# H1maria_v5.net
KiCad netlist of a schematic drawn in EAGLE
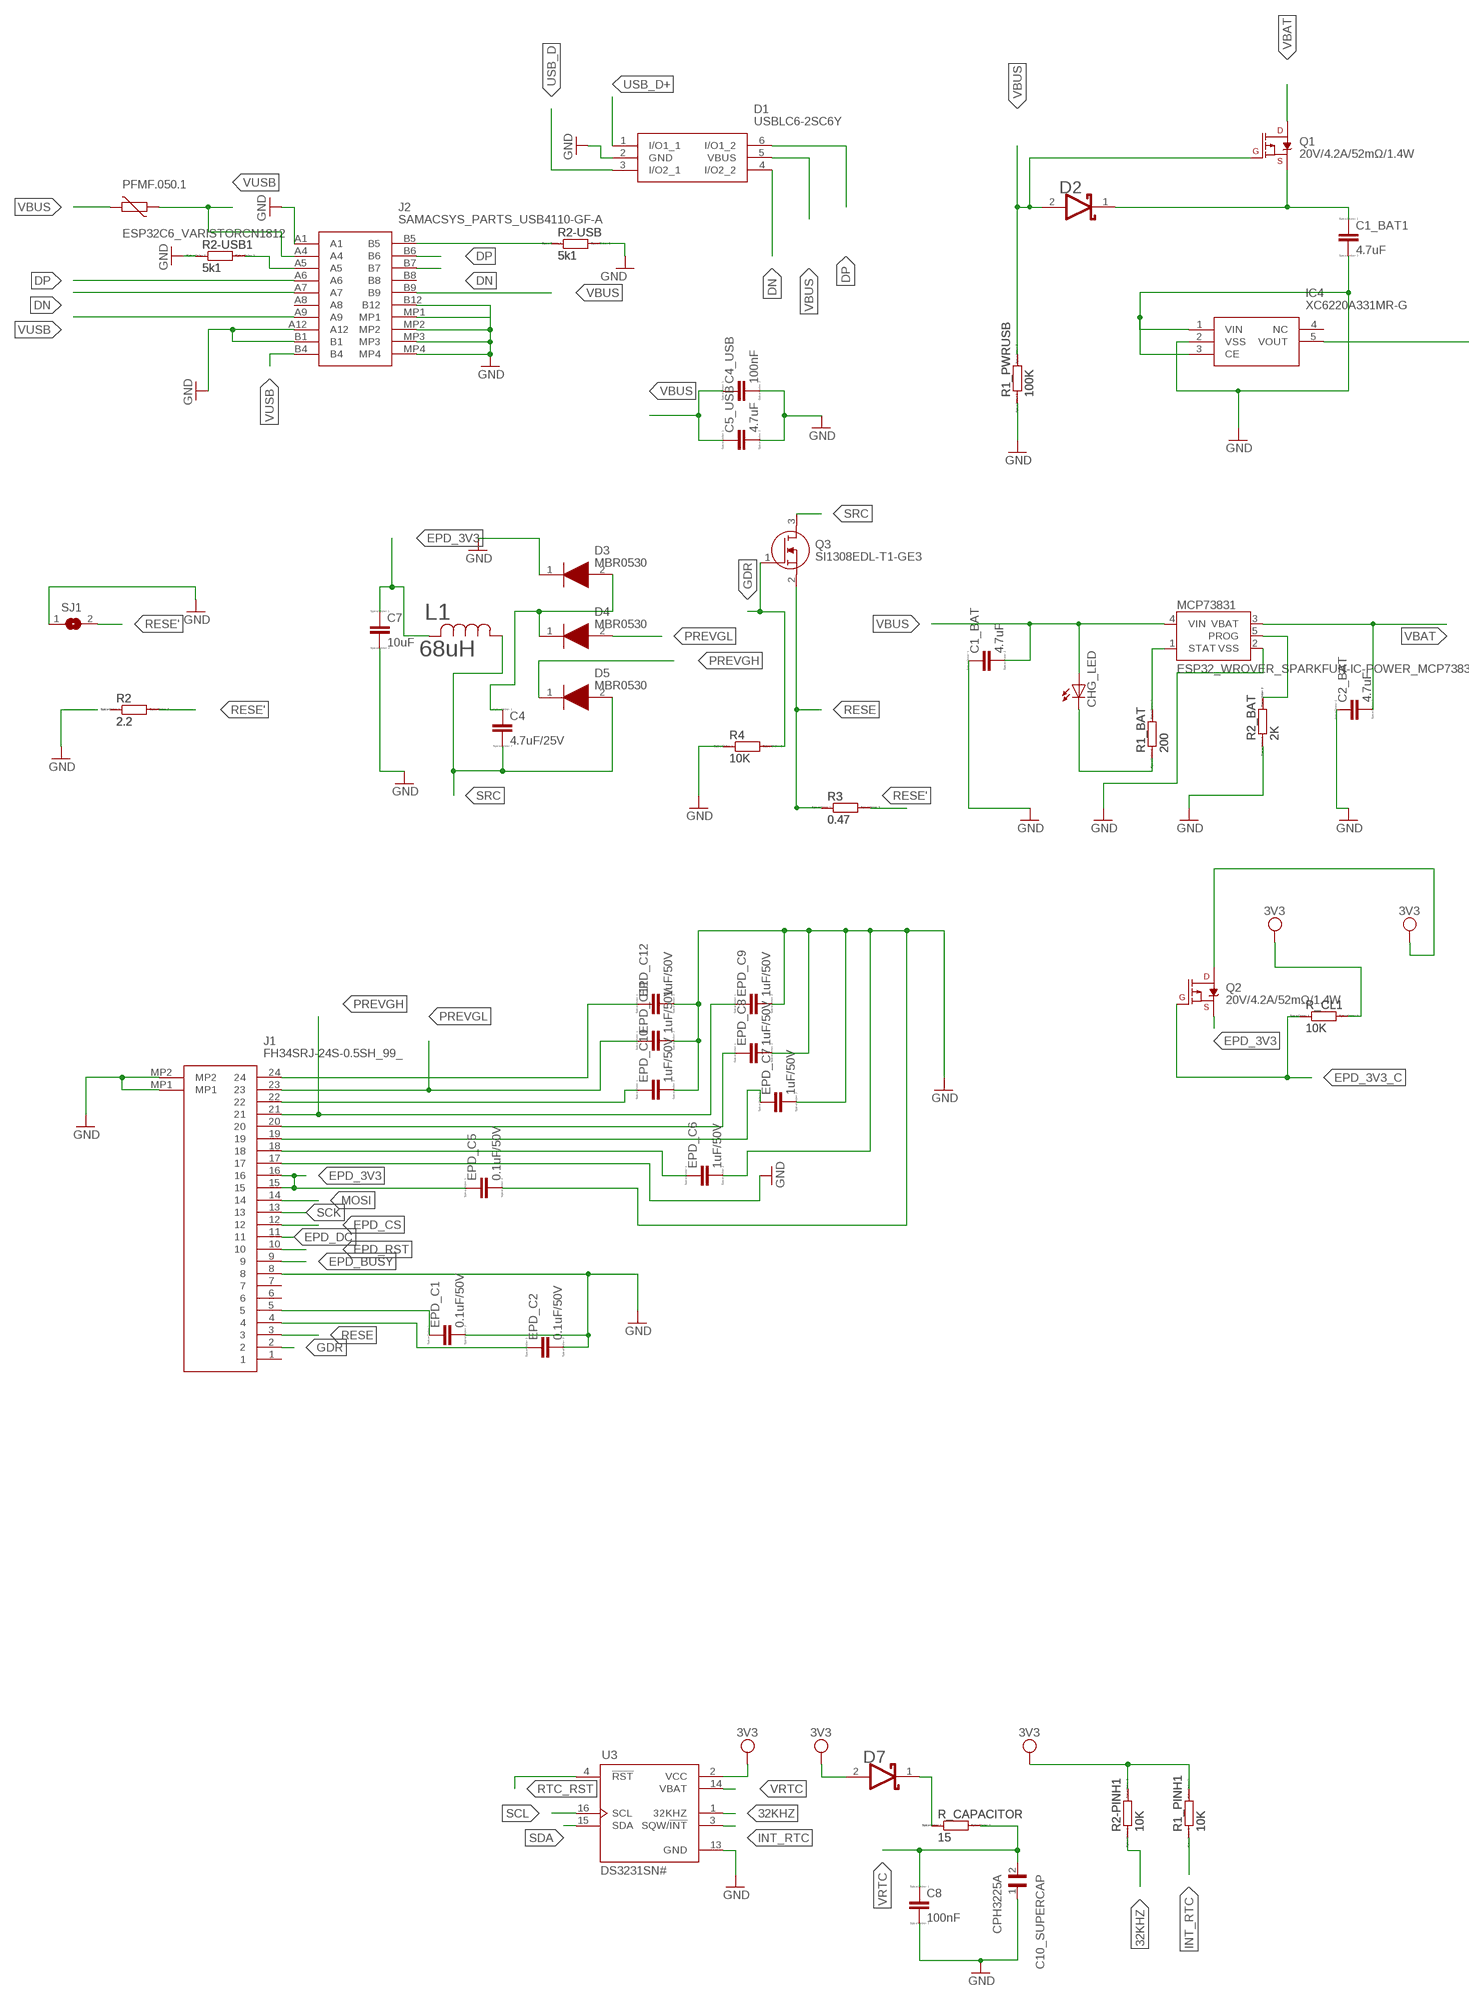
[diagram p0: schematic, sheet 1, part 1 of 2]
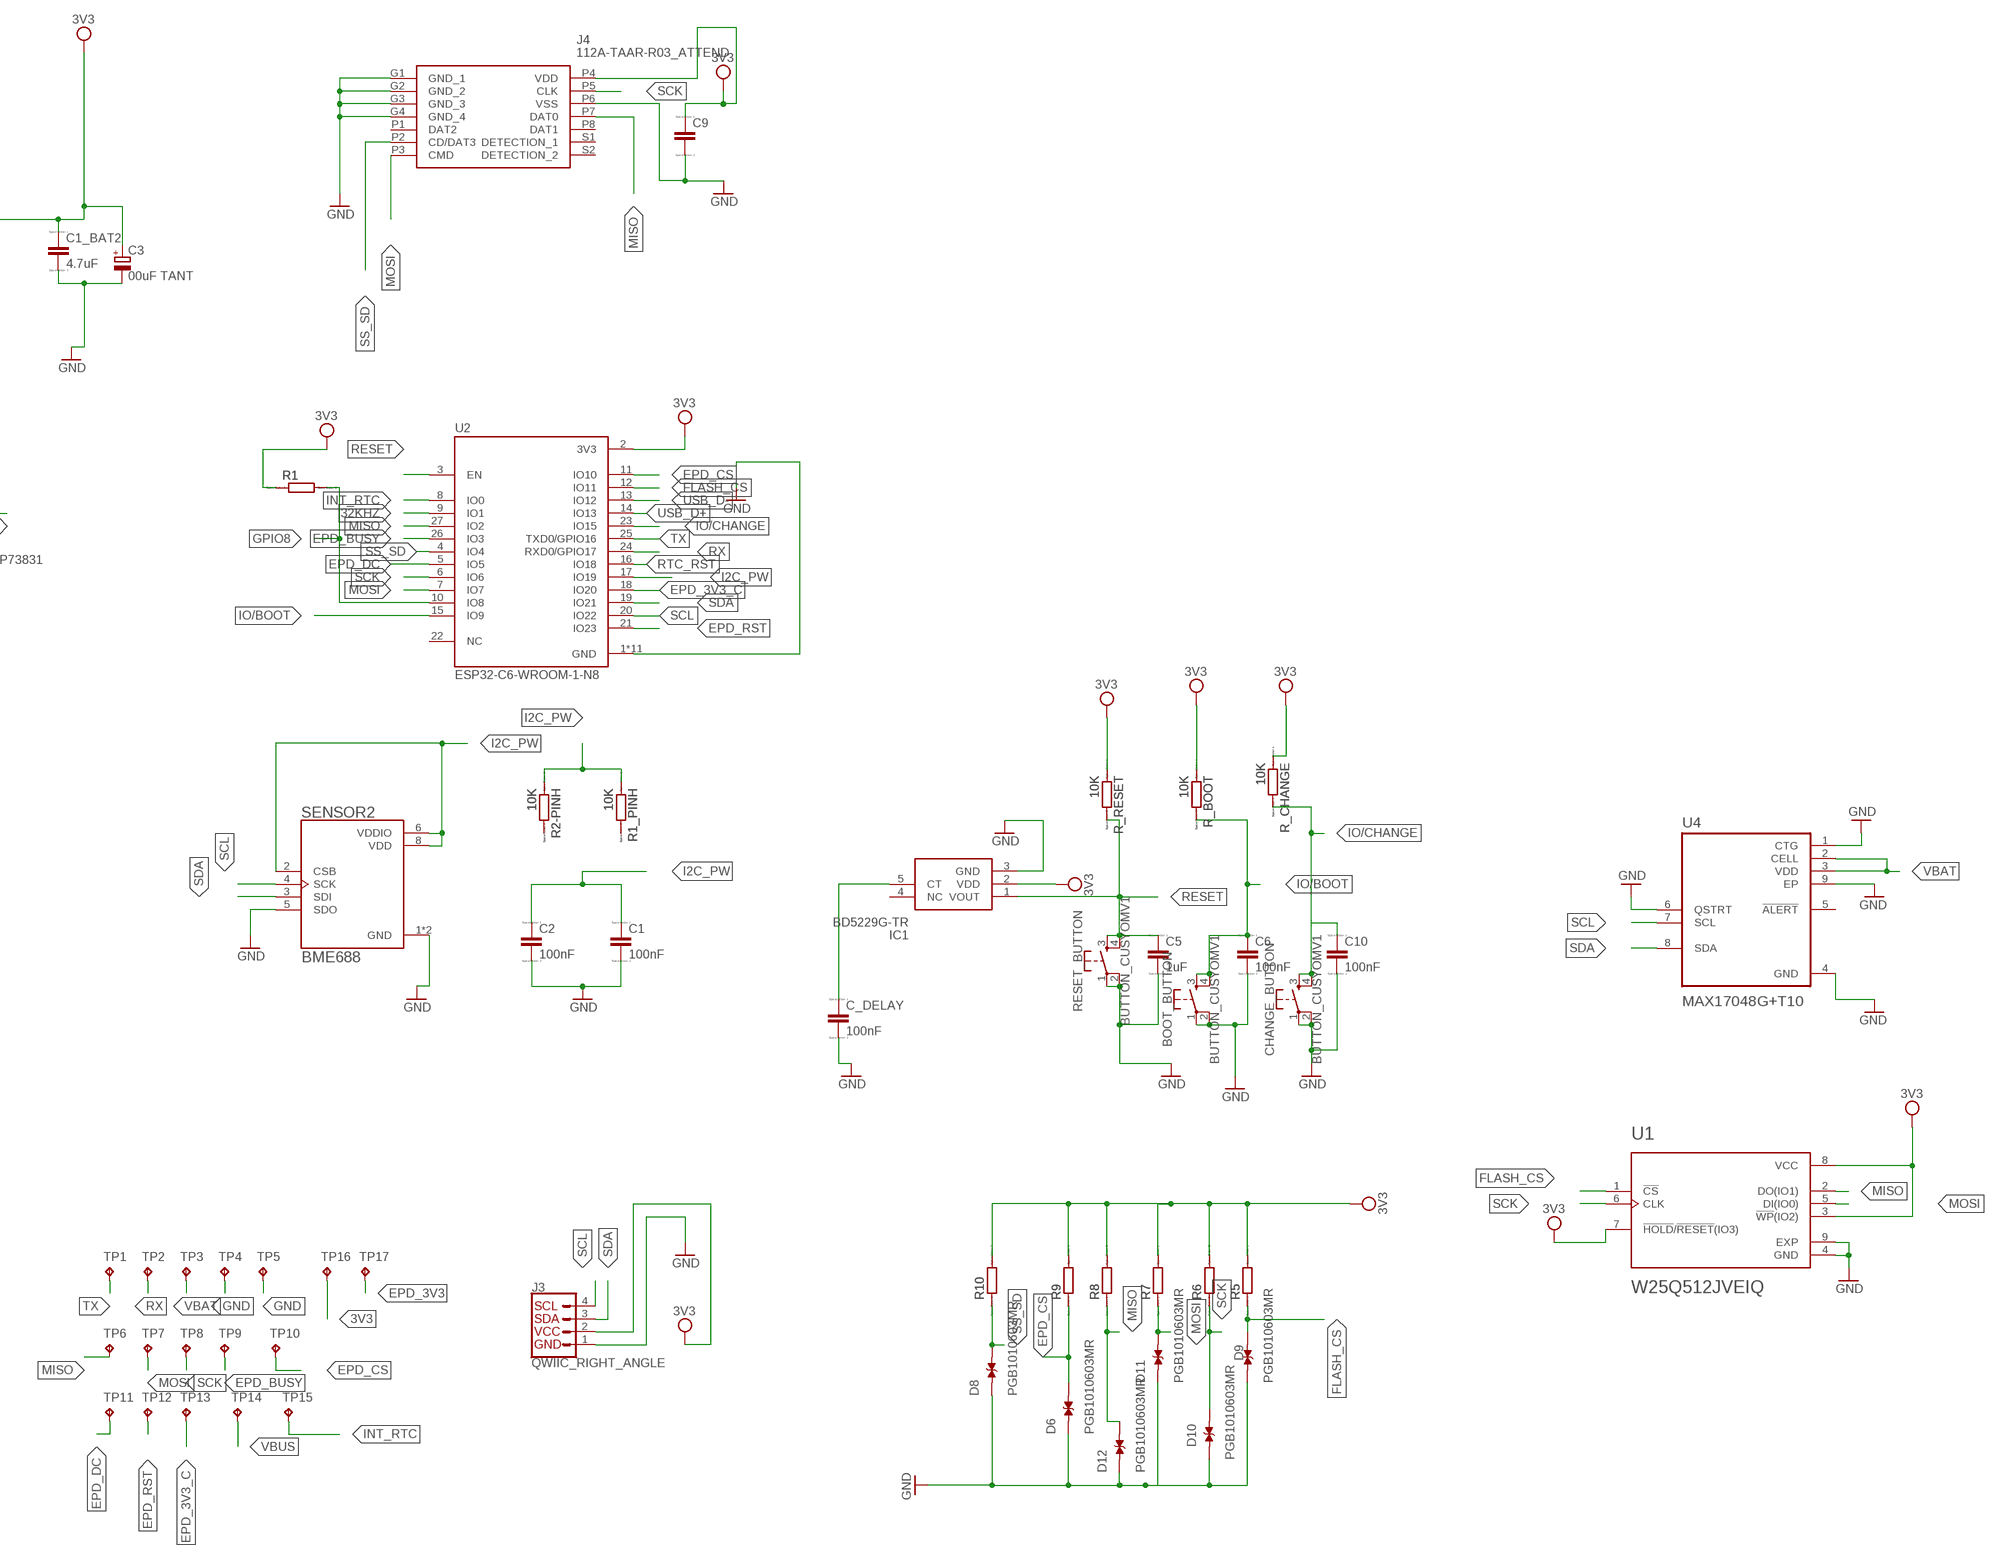
[diagram p1: schematic, sheet 1, part 2 of 2]

(export (version "E")
  (design (tool "Eeschema 10.0.6"))
  (components
    (comp (ref "BOOT_BUTTON")
      (value "BUTTON_CUSYOMV1")
      (footprint "eagle-import:MYBUTTON")
      (libsource (lib "eagle-import") (part "BUTTON_CUSYOMV1"))
    )
    (comp (ref "C1")
      (value "100nF")
      (footprint "eagle-import:ESP32_WROVER_EAGLE-LTSPICE_C0402")
      (libsource (lib "eagle-import") (part "ESP32_WROVER_EAGLE-LTSPICE_CC0402"))
    )
    (comp (ref "C1_BAT")
      (value "4.7uF")
      (footprint "eagle-import:EAGLE-LTSPICE_C0402")
      (libsource (lib "eagle-import") (part "EAGLE-LTSPICE_CC0402"))
    )
    (comp (ref "C1_BAT1")
      (value "4.7uF")
      (footprint "eagle-import:EAGLE-LTSPICE_C0402")
      (libsource (lib "eagle-import") (part "EAGLE-LTSPICE_CC0402"))
    )
    (comp (ref "C1_BAT2")
      (value "4.7uF")
      (footprint "eagle-import:EAGLE-LTSPICE_C0402")
      (libsource (lib "eagle-import") (part "EAGLE-LTSPICE_CC0402"))
    )
    (comp (ref "C2")
      (value "100nF")
      (footprint "eagle-import:ESP32_WROVER_EAGLE-LTSPICE_C0402")
      (libsource (lib "eagle-import") (part "ESP32_WROVER_EAGLE-LTSPICE_CC0402"))
    )
    (comp (ref "C2_BAT")
      (value "4.7uF")
      (footprint "eagle-import:EAGLE-LTSPICE_C0402")
      (libsource (lib "eagle-import") (part "EAGLE-LTSPICE_CC0402"))
    )
    (comp (ref "C3")
      (value "00uF TANT")
      (footprint "eagle-import:RCL_CT3528")
      (libsource (lib "eagle-import") (part "RCL_CPOL-EUCT3528"))
    )
    (comp (ref "C4")
      (value "4.7uF/25V")
      (footprint "eagle-import:ESP32_WROVER_EAGLE-LTSPICE_C0402")
      (libsource (lib "eagle-import") (part "ESP32_WROVER_EAGLE-LTSPICE_CC0402"))
    )
    (comp (ref "C4_USB")
      (value "100nF")
      (footprint "eagle-import:EAGLE-LTSPICE_C0402")
      (libsource (lib "eagle-import") (part "EAGLE-LTSPICE_CC0402"))
    )
    (comp (ref "C5")
      (value "1uF")
      (footprint "eagle-import:EAGLE-LTSPICE_C0402")
      (libsource (lib "eagle-import") (part "EAGLE-LTSPICE_CC0402"))
    )
    (comp (ref "C5_USB")
      (value "4.7uF")
      (footprint "eagle-import:EAGLE-LTSPICE_C0402")
      (libsource (lib "eagle-import") (part "EAGLE-LTSPICE_CC0402"))
    )
    (comp (ref "C6")
      (value "100nF")
      (footprint "eagle-import:EAGLE-LTSPICE_C0402")
      (libsource (lib "eagle-import") (part "EAGLE-LTSPICE_CC0402"))
    )
    (comp (ref "C7")
      (value "10uF")
      (footprint "eagle-import:ESP32_WROVER_EAGLE-LTSPICE_C0402")
      (libsource (lib "eagle-import") (part "ESP32_WROVER_EAGLE-LTSPICE_CC0402"))
    )
    (comp (ref "C8")
      (value "100nF")
      (footprint "eagle-import:EAGLE-LTSPICE_C0402")
      (libsource (lib "eagle-import") (part "EAGLE-LTSPICE_CC0402"))
    )
    (comp (ref "C9")
      (value "ESP32_WROVER_EAGLE-LTSPICE_CC0402")
      (footprint "eagle-import:ESP32_WROVER_EAGLE-LTSPICE_C0402")
      (libsource (lib "eagle-import") (part "ESP32_WROVER_EAGLE-LTSPICE_CC0402"))
    )
    (comp (ref "C10")
      (value "100nF")
      (footprint "eagle-import:EAGLE-LTSPICE_C0402")
      (libsource (lib "eagle-import") (part "EAGLE-LTSPICE_CC0402"))
    )
    (comp (ref "C10_SUPERCAP")
      (value "CPH3225A")
      (footprint "eagle-import:CAPCP3225X100N")
      (fields (field (name "MF") "Seiko Instruments"))
      (libsource (lib "eagle-import") (part "CPH3225A"))
    )
    (comp (ref "CHANGE_BUTTON")
      (value "BUTTON_CUSYOMV1")
      (footprint "eagle-import:MYBUTTON")
      (libsource (lib "eagle-import") (part "BUTTON_CUSYOMV1"))
    )
    (comp (ref "CHG_LED")
      (value "ADAFRUIT_LEDCHIP-LED0603")
      (footprint "eagle-import:ADAFRUIT_CHIP-LED0603")
      (libsource (lib "eagle-import") (part "ADAFRUIT_LEDCHIP-LED0603"))
    )
    (comp (ref "C_DELAY")
      (value "100nF")
      (footprint "eagle-import:EAGLE-LTSPICE_C0402")
      (libsource (lib "eagle-import") (part "EAGLE-LTSPICE_CC0402"))
    )
    (comp (ref "D1")
      (value "USBLC6-2SC6Y")
      (footprint "eagle-import:SOT95P280X145-6N")
      (fields (field (name "MF") "STMicroelectronics"))
      (libsource (lib "eagle-import") (part "USBLC6-2SC6Y"))
    )
    (comp (ref "D2")
      (value "SD0805S020S1R0")
      (footprint "eagle-import:ESP32_WROVER_AVX---SD0805S020S1R0_AVX_SD0805S020S1R0_0")
      (fields
        (field (name "DIGIKEY_PART_NUMBER") "478-7800-1-ND")
        (field (name "MF") "AVX")
        (field (name "MOUSER_PART_NUMBER") "581-SD0805S020S1R0")
      )
      (libsource (lib "eagle-import") (part "ESP32_WROVER_AVX---SD0805S020S1R0_AVX_SD0805S020S1R0_0_0AVX_SD0805S020S1R0_0_0"))
    )
    (comp (ref "D3")
      (value "MBR0530")
      (footprint "eagle-import:SOD3716X135N")
      (fields (field (name "MF") "ON Semiconductor"))
      (libsource (lib "eagle-import") (part "MBR0530"))
    )
    (comp (ref "D4")
      (value "MBR0530")
      (footprint "eagle-import:SOD3716X135N")
      (fields (field (name "MF") "ON Semiconductor"))
      (libsource (lib "eagle-import") (part "MBR0530"))
    )
    (comp (ref "D5")
      (value "MBR0530")
      (footprint "eagle-import:SOD3716X135N")
      (fields (field (name "MF") "ON Semiconductor"))
      (libsource (lib "eagle-import") (part "MBR0530"))
    )
    (comp (ref "D6")
      (value "PGB1010603MR")
      (footprint "eagle-import:DIOC1608X36N")
      (fields (field (name "MF") "Littelfuse Inc."))
      (libsource (lib "eagle-import") (part "PGB1010603MR"))
    )
    (comp (ref "D7")
      (value "ESP32_WROVER_AVX---SD0805S020S1R0_AVX_SD0805S020S1R0_0_0AVX_SD0805S020S1R0_0_0")
      (footprint "eagle-import:ESP32_WROVER_AVX---SD0805S020S1R0_AVX_SD0805S020S1R0_0")
      (fields
        (field (name "DIGIKEY_PART_NUMBER") "478-7800-1-ND")
        (field (name "MF") "AVX")
        (field (name "MOUSER_PART_NUMBER") "581-SD0805S020S1R0")
      )
      (libsource (lib "eagle-import") (part "ESP32_WROVER_AVX---SD0805S020S1R0_AVX_SD0805S020S1R0_0_0AVX_SD0805S020S1R0_0_0"))
    )
    (comp (ref "D8")
      (value "PGB1010603MR")
      (footprint "eagle-import:DIOC1608X36N")
      (fields (field (name "MF") "Littelfuse Inc."))
      (libsource (lib "eagle-import") (part "PGB1010603MR"))
    )
    (comp (ref "D9")
      (value "PGB1010603MR")
      (footprint "eagle-import:DIOC1608X36N")
      (fields (field (name "MF") "Littelfuse Inc."))
      (libsource (lib "eagle-import") (part "PGB1010603MR"))
    )
    (comp (ref "D10")
      (value "PGB1010603MR")
      (footprint "eagle-import:DIOC1608X36N")
      (fields (field (name "MF") "Littelfuse Inc."))
      (libsource (lib "eagle-import") (part "PGB1010603MR"))
    )
    (comp (ref "D11")
      (value "PGB1010603MR")
      (footprint "eagle-import:DIOC1608X36N")
      (fields (field (name "MF") "Littelfuse Inc."))
      (libsource (lib "eagle-import") (part "PGB1010603MR"))
    )
    (comp (ref "D12")
      (value "PGB1010603MR")
      (footprint "eagle-import:DIOC1608X36N")
      (fields (field (name "MF") "Littelfuse Inc."))
      (libsource (lib "eagle-import") (part "PGB1010603MR"))
    )
    (comp (ref "EPD_C1")
      (value "0.1uF/50V")
      (footprint "eagle-import:EAGLE-LTSPICE_C0402")
      (libsource (lib "eagle-import") (part "EAGLE-LTSPICE_CC0402"))
    )
    (comp (ref "EPD_C2")
      (value "0.1uF/50V")
      (footprint "eagle-import:EAGLE-LTSPICE_C0402")
      (libsource (lib "eagle-import") (part "EAGLE-LTSPICE_CC0402"))
    )
    (comp (ref "EPD_C5")
      (value "0.1uF/50V")
      (footprint "eagle-import:EAGLE-LTSPICE_C0402")
      (libsource (lib "eagle-import") (part "EAGLE-LTSPICE_CC0402"))
    )
    (comp (ref "EPD_C6")
      (value "1uF/50V")
      (footprint "eagle-import:EAGLE-LTSPICE_C0402")
      (libsource (lib "eagle-import") (part "EAGLE-LTSPICE_CC0402"))
    )
    (comp (ref "EPD_C7")
      (value "1uF/50V")
      (footprint "eagle-import:EAGLE-LTSPICE_C0402")
      (libsource (lib "eagle-import") (part "EAGLE-LTSPICE_CC0402"))
    )
    (comp (ref "EPD_C8")
      (value "1uF/50V")
      (footprint "eagle-import:EAGLE-LTSPICE_C0402")
      (libsource (lib "eagle-import") (part "EAGLE-LTSPICE_CC0402"))
    )
    (comp (ref "EPD_C9")
      (value "1uF/50V")
      (footprint "eagle-import:EAGLE-LTSPICE_C0402")
      (libsource (lib "eagle-import") (part "EAGLE-LTSPICE_CC0402"))
    )
    (comp (ref "EPD_C10")
      (value "1uF/50V")
      (footprint "eagle-import:EAGLE-LTSPICE_C0402")
      (libsource (lib "eagle-import") (part "EAGLE-LTSPICE_CC0402"))
    )
    (comp (ref "EPD_C11")
      (value "1uF/50V")
      (footprint "eagle-import:EAGLE-LTSPICE_C0402")
      (libsource (lib "eagle-import") (part "EAGLE-LTSPICE_CC0402"))
    )
    (comp (ref "EPD_C12")
      (value "1uF/50V")
      (footprint "eagle-import:EAGLE-LTSPICE_C0402")
      (libsource (lib "eagle-import") (part "EAGLE-LTSPICE_CC0402"))
    )
    (comp (ref "IC1")
      (value "BD5229G-TR")
      (footprint "eagle-import:SOT95P280X125-5N")
      (fields (field (name "MOUSER_PART_NUMBER") "755-BD5229G-TR"))
      (libsource (lib "eagle-import") (part "BD5229G-TR"))
    )
    (comp (ref "IC4")
      (value "XC6220A331MR-G")
      (footprint "eagle-import:SOT95P280X120-5N")
      (fields (field (name "MOUSER_PART_NUMBER") "865-XC6220A331MR-G"))
      (libsource (lib "eagle-import") (part "XC6220A331MR-G"))
    )
    (comp (ref "J1")
      (value "FH34SRJ-24S-0.5SH_99_")
      (footprint "eagle-import:FH34SRJ24S05SH99")
      (fields
        (field (name "MANUFACTURER_PART_NUMBER") "FH34SRJ-24S-0.5SH(99)")
        (field (name "MOUSER_PART_NUMBER") "798-FH34SRJ24S05SH99")
      )
      (libsource (lib "eagle-import") (part "FH34SRJ-24S-0.5SH_99_"))
    )
    (comp (ref "J2")
      (value "SAMACSYS_PARTS_USB4110-GF-A")
      (footprint "eagle-import:SAMACSYS_PARTS_USB4110GFA")
      (fields
        (field (name "MANUFACTURER_PART_NUMBER") "USB4110-GF-A")
        (field (name "MOUSER_PART_NUMBER") "640-USB4110-GF-A")
      )
      (libsource (lib "eagle-import") (part "SAMACSYS_PARTS_USB4110-GF-A"))
    )
    (comp (ref "J3")
      (value "QWIIC_RIGHT_ANGLE")
      (footprint "eagle-import:JST04_1MM_RA")
      (libsource (lib "eagle-import") (part "QWIIC_CONNECTORJS-1MM"))
    )
    (comp (ref "J4")
      (value "112A-TAAR-R03_ATTEND")
      (footprint "eagle-import:112ATAARR03ATTEND")
      (fields (field (name "MANUFACTURER_PART_NUMBER") "112A-TAAR-R03 ATTEND"))
      (libsource (lib "eagle-import") (part "112A-TAAR-R03_ATTEND"))
    )
    (comp (ref "L1")
      (value "68uH")
      (footprint "eagle-import:IND_4828-WE-TPC_WRE")
      (fields
        (field (name "MANUFACTURER_PART_NUMBER") "744043680")
        (field (name "COPYRIGHT") "Copyright (C) 2024 Ultra Librarian. All rights reserved.")
      )
      (libsource (lib "eagle-import") (part "744043680IND_4828-WE-TPC_WRE"))
    )
    (comp (ref "MCP73831")
      (value "ESP32_WROVER_SPARKFUN-IC-POWER_MCP73831")
      (footprint "eagle-import:ESP32_WROVER_SPARKFUN-IC-POWER_SOT23-5")
      (libsource (lib "eagle-import") (part "ESP32_WROVER_SPARKFUN-IC-POWER_MCP73831"))
    )
    (comp (ref "PFMF.050.1")
      (value "ESP32C6_VARISTORCN1812")
      (footprint "eagle-import:ESP32C6_VARISTOR_CT_CN1812")
      (libsource (lib "eagle-import") (part "ESP32C6_VARISTORCN1812"))
    )
    (comp (ref "Q1")
      (value "20V/4.2A/52mΩ/1.4W")
      (footprint "eagle-import:ESP32_WROVER_SPARKFUN-DISCRETESEMI_SOT23-3")
      (libsource (lib "eagle-import") (part "ESP32_WROVER_SPARKFUN-DISCRETESEMI_MOSFET_PCH-DMG2305UX-7"))
    )
    (comp (ref "Q2")
      (value "20V/4.2A/52mΩ/1.4W")
      (footprint "eagle-import:ESP32_WROVER_SPARKFUN-DISCRETESEMI_SOT23-3")
      (libsource (lib "eagle-import") (part "ESP32_WROVER_SPARKFUN-DISCRETESEMI_MOSFET_PCH-DMG2305UX-7"))
    )
    (comp (ref "Q3")
      (value "SI1308EDL-T1-GE3")
      (footprint "eagle-import:SOT65P210X110-3N")
      (fields (field (name "MF") "Vishay Siliconix"))
      (libsource (lib "eagle-import") (part "SI1308EDL-T1-GE3"))
    )
    (comp (ref "R1")
      (value "ESP32_WROVER_EAGLE-LTSPICE_RR0402")
      (footprint "eagle-import:ESP32_WROVER_EAGLE-LTSPICE_R0402")
      (libsource (lib "eagle-import") (part "ESP32_WROVER_EAGLE-LTSPICE_RR0402"))
    )
    (comp (ref "R1_BAT")
      (value "200")
      (footprint "eagle-import:ESP32_WROVER_EAGLE-LTSPICE_R0402")
      (libsource (lib "eagle-import") (part "ESP32_WROVER_EAGLE-LTSPICE_RR0402"))
    )
    (comp (ref "R1_PINH")
      (value "10K")
      (footprint "eagle-import:ESP32_WROVER_EAGLE-LTSPICE_R0402")
      (libsource (lib "eagle-import") (part "ESP32_WROVER_EAGLE-LTSPICE_RR0402"))
    )
    (comp (ref "R1_PINH1")
      (value "10K")
      (footprint "eagle-import:ESP32_WROVER_EAGLE-LTSPICE_R0402")
      (libsource (lib "eagle-import") (part "ESP32_WROVER_EAGLE-LTSPICE_RR0402"))
    )
    (comp (ref "R1_PWRUSB")
      (value "100K")
      (footprint "eagle-import:ESP32_WROVER_EAGLE-LTSPICE_R0402")
      (libsource (lib "eagle-import") (part "ESP32_WROVER_EAGLE-LTSPICE_RR0402"))
    )
    (comp (ref "R2")
      (value "2.2")
      (footprint "eagle-import:ESP32_WROVER_EAGLE-LTSPICE_R0402")
      (libsource (lib "eagle-import") (part "ESP32_WROVER_EAGLE-LTSPICE_RR0402"))
    )
    (comp (ref "R2-PINH")
      (value "10K")
      (footprint "eagle-import:ESP32_WROVER_EAGLE-LTSPICE_R0402")
      (libsource (lib "eagle-import") (part "ESP32_WROVER_EAGLE-LTSPICE_RR0402"))
    )
    (comp (ref "R2-PINH1")
      (value "10K")
      (footprint "eagle-import:ESP32_WROVER_EAGLE-LTSPICE_R0402")
      (libsource (lib "eagle-import") (part "ESP32_WROVER_EAGLE-LTSPICE_RR0402"))
    )
    (comp (ref "R2-USB")
      (value "5k1")
      (footprint "eagle-import:ESP32_WROVER_EAGLE-LTSPICE_R0402")
      (libsource (lib "eagle-import") (part "ESP32_WROVER_EAGLE-LTSPICE_RR0402"))
    )
    (comp (ref "R2-USB1")
      (value "5k1")
      (footprint "eagle-import:ESP32_WROVER_EAGLE-LTSPICE_R0402")
      (libsource (lib "eagle-import") (part "ESP32_WROVER_EAGLE-LTSPICE_RR0402"))
    )
    (comp (ref "R2_BAT")
      (value "2K")
      (footprint "eagle-import:ESP32_WROVER_EAGLE-LTSPICE_R0402")
      (libsource (lib "eagle-import") (part "ESP32_WROVER_EAGLE-LTSPICE_RR0402"))
    )
    (comp (ref "R3")
      (value "0.47")
      (footprint "eagle-import:ESP32_WROVER_EAGLE-LTSPICE_R0402")
      (libsource (lib "eagle-import") (part "ESP32_WROVER_EAGLE-LTSPICE_RR0402"))
    )
    (comp (ref "R4")
      (value "10K")
      (footprint "eagle-import:ESP32_WROVER_EAGLE-LTSPICE_R0402")
      (libsource (lib "eagle-import") (part "ESP32_WROVER_EAGLE-LTSPICE_RR0402"))
    )
    (comp (ref "R5")
      (value "ESP32_WROVER_EAGLE-LTSPICE_RR0402")
      (footprint "eagle-import:ESP32_WROVER_EAGLE-LTSPICE_R0402")
      (libsource (lib "eagle-import") (part "ESP32_WROVER_EAGLE-LTSPICE_RR0402"))
    )
    (comp (ref "R6")
      (value "ESP32_WROVER_EAGLE-LTSPICE_RR0402")
      (footprint "eagle-import:ESP32_WROVER_EAGLE-LTSPICE_R0402")
      (libsource (lib "eagle-import") (part "ESP32_WROVER_EAGLE-LTSPICE_RR0402"))
    )
    (comp (ref "R7")
      (value "ESP32_WROVER_EAGLE-LTSPICE_RR0402")
      (footprint "eagle-import:ESP32_WROVER_EAGLE-LTSPICE_R0402")
      (libsource (lib "eagle-import") (part "ESP32_WROVER_EAGLE-LTSPICE_RR0402"))
    )
    (comp (ref "R8")
      (value "ESP32_WROVER_EAGLE-LTSPICE_RR0402")
      (footprint "eagle-import:ESP32_WROVER_EAGLE-LTSPICE_R0402")
      (libsource (lib "eagle-import") (part "ESP32_WROVER_EAGLE-LTSPICE_RR0402"))
    )
    (comp (ref "R9")
      (value "ESP32_WROVER_EAGLE-LTSPICE_RR0402")
      (footprint "eagle-import:ESP32_WROVER_EAGLE-LTSPICE_R0402")
      (libsource (lib "eagle-import") (part "ESP32_WROVER_EAGLE-LTSPICE_RR0402"))
    )
    (comp (ref "R10")
      (value "ESP32_WROVER_EAGLE-LTSPICE_RR0402")
      (footprint "eagle-import:ESP32_WROVER_EAGLE-LTSPICE_R0402")
      (libsource (lib "eagle-import") (part "ESP32_WROVER_EAGLE-LTSPICE_RR0402"))
    )
    (comp (ref "RESET_BUTTON")
      (value "BUTTON_CUSYOMV1")
      (footprint "eagle-import:MYBUTTON")
      (libsource (lib "eagle-import") (part "BUTTON_CUSYOMV1"))
    )
    (comp (ref "R_BOOT")
      (value "10K")
      (footprint "eagle-import:ESP32_WROVER_EAGLE-LTSPICE_R0402")
      (libsource (lib "eagle-import") (part "ESP32_WROVER_EAGLE-LTSPICE_RR0402"))
    )
    (comp (ref "R_CAPACITOR")
      (value "15")
      (footprint "eagle-import:ESP32_WROVER_EAGLE-LTSPICE_R0402")
      (libsource (lib "eagle-import") (part "ESP32_WROVER_EAGLE-LTSPICE_RR0402"))
    )
    (comp (ref "R_CHANGE")
      (value "10K")
      (footprint "eagle-import:ESP32_WROVER_EAGLE-LTSPICE_R0402")
      (libsource (lib "eagle-import") (part "ESP32_WROVER_EAGLE-LTSPICE_RR0402"))
    )
    (comp (ref "R_CL1")
      (value "10K")
      (footprint "eagle-import:ESP32_WROVER_EAGLE-LTSPICE_R0402")
      (libsource (lib "eagle-import") (part "ESP32_WROVER_EAGLE-LTSPICE_RR0402"))
    )
    (comp (ref "R_RESET")
      (value "10K")
      (footprint "eagle-import:ESP32_WROVER_EAGLE-LTSPICE_R0402")
      (libsource (lib "eagle-import") (part "ESP32_WROVER_EAGLE-LTSPICE_RR0402"))
    )
    (comp (ref "SENSOR2")
      (value "BME688")
      (footprint "eagle-import:ESP32_WROVER_BME680_PSON80P300X300X100-8N")
      (fields (field (name "MF") "Bosch Sensortec") (field (name "MP") "BME680"))
      (libsource (lib "eagle-import") (part "ESP32_WROVER_BME680_BME680"))
    )
    (comp (ref "SJ1") (value "SJ") (footprint "eagle-import:SJ") (libsource (lib "eagle-import") (part "SJ")))
    (comp (ref "TP1")
      (value "TPTP20R")
      (footprint "eagle-import:TP20R")
      (libsource (lib "eagle-import") (part "TPTP20R"))
    )
    (comp (ref "TP2")
      (value "TPTP20R")
      (footprint "eagle-import:TP20R")
      (libsource (lib "eagle-import") (part "TPTP20R"))
    )
    (comp (ref "TP3")
      (value "TPTP20R")
      (footprint "eagle-import:TP20R")
      (libsource (lib "eagle-import") (part "TPTP20R"))
    )
    (comp (ref "TP4")
      (value "TPTP20R")
      (footprint "eagle-import:TP20R")
      (libsource (lib "eagle-import") (part "TPTP20R"))
    )
    (comp (ref "TP5")
      (value "TPTP20R")
      (footprint "eagle-import:TP20R")
      (libsource (lib "eagle-import") (part "TPTP20R"))
    )
    (comp (ref "TP6")
      (value "TPTP20R")
      (footprint "eagle-import:TP20R")
      (libsource (lib "eagle-import") (part "TPTP20R"))
    )
    (comp (ref "TP7")
      (value "TPTP20R")
      (footprint "eagle-import:TP20R")
      (libsource (lib "eagle-import") (part "TPTP20R"))
    )
    (comp (ref "TP8")
      (value "TPTP20R")
      (footprint "eagle-import:TP20R")
      (libsource (lib "eagle-import") (part "TPTP20R"))
    )
    (comp (ref "TP9")
      (value "TPTP20R")
      (footprint "eagle-import:TP20R")
      (libsource (lib "eagle-import") (part "TPTP20R"))
    )
    (comp (ref "TP10")
      (value "TPTP20R")
      (footprint "eagle-import:TP20R")
      (libsource (lib "eagle-import") (part "TPTP20R"))
    )
    (comp (ref "TP11")
      (value "TPTP20R")
      (footprint "eagle-import:TP20R")
      (libsource (lib "eagle-import") (part "TPTP20R"))
    )
    (comp (ref "TP12")
      (value "TPTP20R")
      (footprint "eagle-import:TP20R")
      (libsource (lib "eagle-import") (part "TPTP20R"))
    )
    (comp (ref "TP13")
      (value "TPTP20R")
      (footprint "eagle-import:TP20R")
      (libsource (lib "eagle-import") (part "TPTP20R"))
    )
    (comp (ref "TP14")
      (value "TPTP20R")
      (footprint "eagle-import:TP20R")
      (libsource (lib "eagle-import") (part "TPTP20R"))
    )
    (comp (ref "TP15")
      (value "TPTP20R")
      (footprint "eagle-import:TP20R")
      (libsource (lib "eagle-import") (part "TPTP20R"))
    )
    (comp (ref "TP16")
      (value "TPTP20R")
      (footprint "eagle-import:TP20R")
      (libsource (lib "eagle-import") (part "TPTP20R"))
    )
    (comp (ref "TP17")
      (value "TPTP20R")
      (footprint "eagle-import:TP20R")
      (libsource (lib "eagle-import") (part "TPTP20R"))
    )
    (comp (ref "U1")
      (value "W25Q512JVEIQ")
      (footprint "eagle-import:SON127P600X800X80-9N")
      (fields (field (name "MF") "Winbond Electronics"))
      (libsource (lib "eagle-import") (part "W25Q512JVEIQ"))
    )
    (comp (ref "U2")
      (value "ESP32-C6-WROOM-1-N8")
      (footprint "eagle-import:XCVR_ESP32-C6-WROOM-1-N8")
      (fields (field (name "MF") "Espressif Systems"))
      (libsource (lib "eagle-import") (part "ESP32-C6-WROOM-1-N8"))
    )
    (comp (ref "U3")
      (value "DS3231SN#")
      (footprint "eagle-import:SOIC127P1032X265-16N")
      (fields (field (name "MF") "Analog Devices"))
      (libsource (lib "eagle-import") (part "DS3231SN#"))
    )
    (comp (ref "U4")
      (value "MAX17048G+T10")
      (footprint "eagle-import:SON50P200X200X80-9N")
      (fields (field (name "MF") "Analog Devices"))
      (libsource (lib "eagle-import") (part "MAX17048G+T10"))
    )
  )
  (nets
    (net (code "1") (name "3V3") (class "Default")
      (node (ref "C1_BAT2") (pin "1") (pinfunction "1_1") (pintype "passive"))
      (node (ref "C3") (pin "+") (pinfunction "+_+") (pintype "passive"))
      (node (ref "C9") (pin "1") (pinfunction "1_1") (pintype "passive"))
      (node (ref "D7") (pin "2") (pinfunction "ANODE_2") (pintype "bidirectional"))
      (node (ref "IC1") (pin "2") (pinfunction "VDD_2") (pintype "bidirectional"))
      (node (ref "IC4") (pin "5") (pinfunction "VOUT_5") (pintype "bidirectional"))
      (node (ref "J3") (pin "2") (pinfunction "2_2") (pintype "power_in"))
      (node (ref "J4") (pin "P4") (pinfunction "VDD_P4") (pintype "bidirectional"))
      (node (ref "Q2") (pin "3") (pinfunction "D_3") (pintype "bidirectional"))
      (node (ref "R1") (pin "1") (pinfunction "1_1") (pintype "passive"))
      (node (ref "R10") (pin "2") (pinfunction "2_2") (pintype "passive"))
      (node (ref "R1_PINH1") (pin "2") (pinfunction "2_2") (pintype "passive"))
      (node (ref "R2-PINH1") (pin "2") (pinfunction "2_2") (pintype "passive"))
      (node (ref "R5") (pin "2") (pinfunction "2_2") (pintype "passive"))
      (node (ref "R6") (pin "2") (pinfunction "2_2") (pintype "passive"))
      (node (ref "R7") (pin "2") (pinfunction "2_2") (pintype "passive"))
      (node (ref "R8") (pin "2") (pinfunction "2_2") (pintype "passive"))
      (node (ref "R9") (pin "2") (pinfunction "2_2") (pintype "passive"))
      (node (ref "R_BOOT") (pin "1") (pinfunction "1_1") (pintype "passive"))
      (node (ref "R_CHANGE") (pin "1") (pinfunction "1_1") (pintype "passive"))
      (node (ref "R_CL1") (pin "2") (pinfunction "2_2") (pintype "passive"))
      (node (ref "R_RESET") (pin "1") (pinfunction "1_1") (pintype "passive"))
      (node (ref "TP16") (pin "TP") (pinfunction "TP_TP") (pintype "input"))
      (node (ref "U1") (pin "3") (pinfunction "~{WP}(IO2)_3") (pintype "bidirectional"))
      (node (ref "U1") (pin "7") (pinfunction "~{HOLD}/~{RESET}(IO3)_7") (pintype "bidirectional"))
      (node (ref "U1") (pin "8") (pinfunction "VCC_8") (pintype "power_in"))
      (node (ref "U2") (pin "2") (pinfunction "3V3_2") (pintype "power_in"))
      (node (ref "U3") (pin "2") (pinfunction "VCC_2") (pintype "power_in"))
    )
    (net (code "2") (name "32KHZ") (class "Default")
      (node (ref "R2-PINH1") (pin "1") (pinfunction "1_1") (pintype "passive"))
      (node (ref "U2") (pin "9") (pinfunction "IO1_9") (pintype "bidirectional"))
      (node (ref "U3") (pin "1") (pinfunction "32KHZ_1") (pintype "output"))
    )
    (net (code "3") (name "DN") (class "Default")
      (node (ref "D1") (pin "4") (pinfunction "I/O2_2_4") (pintype "bidirectional"))
      (node (ref "J2") (pin "A7") (pinfunction "A7_A7") (pintype "bidirectional"))
      (node (ref "J2") (pin "B7") (pinfunction "B7_B7") (pintype "bidirectional"))
    )
    (net (code "4") (name "DP") (class "Default")
      (node (ref "D1") (pin "6") (pinfunction "I/O1_2_6") (pintype "bidirectional"))
      (node (ref "J2") (pin "A6") (pinfunction "A6_A6") (pintype "bidirectional"))
      (node (ref "J2") (pin "B6") (pinfunction "B6_B6") (pintype "bidirectional"))
    )
    (net (code "5") (name "EPD_3V3") (class "Default")
      (node (ref "C7") (pin "1") (pinfunction "1_1") (pintype "passive"))
      (node (ref "EPD_C5") (pin "1") (pinfunction "1_1") (pintype "passive"))
      (node (ref "J1") (pin "15") (pinfunction "15_15") (pintype "bidirectional"))
      (node (ref "J1") (pin "16") (pinfunction "16_16") (pintype "bidirectional"))
      (node (ref "L1") (pin "2") (pinfunction "2_2") (pintype "passive"))
      (node (ref "Q2") (pin "2") (pinfunction "S_2") (pintype "bidirectional"))
      (node (ref "TP17") (pin "TP") (pinfunction "TP_TP") (pintype "input"))
    )
    (net (code "6") (name "EPD_3V3_C") (class "Default")
      (node (ref "Q2") (pin "1") (pinfunction "G_1") (pintype "bidirectional"))
      (node (ref "R_CL1") (pin "1") (pinfunction "1_1") (pintype "passive"))
      (node (ref "TP13") (pin "TP") (pinfunction "TP_TP") (pintype "input"))
      (node (ref "U2") (pin "18") (pinfunction "IO20_18") (pintype "bidirectional"))
    )
    (net (code "7") (name "EPD_BUSY") (class "Default")
      (node (ref "J1") (pin "9") (pinfunction "9_9") (pintype "bidirectional"))
      (node (ref "TP9") (pin "TP") (pinfunction "TP_TP") (pintype "input"))
      (node (ref "U2") (pin "26") (pinfunction "IO3_26") (pintype "bidirectional"))
    )
    (net (code "8") (name "EPD_CS") (class "Default")
      (node (ref "D6") (pin "2") (pinfunction "2_2") (pintype "passive"))
      (node (ref "J1") (pin "12") (pinfunction "12_12") (pintype "bidirectional"))
      (node (ref "R9") (pin "1") (pinfunction "1_1") (pintype "passive"))
      (node (ref "TP10") (pin "TP") (pinfunction "TP_TP") (pintype "input"))
      (node (ref "U2") (pin "11") (pinfunction "IO10_11") (pintype "bidirectional"))
    )
    (net (code "9") (name "EPD_DC") (class "Default")
      (node (ref "J1") (pin "11") (pinfunction "11_11") (pintype "bidirectional"))
      (node (ref "TP11") (pin "TP") (pinfunction "TP_TP") (pintype "input"))
      (node (ref "U2") (pin "5") (pinfunction "IO5_5") (pintype "bidirectional"))
    )
    (net (code "10") (name "EPD_RST") (class "Default")
      (node (ref "J1") (pin "10") (pinfunction "10_10") (pintype "bidirectional"))
      (node (ref "TP12") (pin "TP") (pinfunction "TP_TP") (pintype "input"))
      (node (ref "U2") (pin "21") (pinfunction "IO23_21") (pintype "bidirectional"))
    )
    (net (code "11") (name "FLASH_CS") (class "Default")
      (node (ref "D9") (pin "2") (pinfunction "2_2") (pintype "passive"))
      (node (ref "R5") (pin "1") (pinfunction "1_1") (pintype "passive"))
      (node (ref "U1") (pin "1") (pinfunction "~{CS}_1") (pintype "input"))
      (node (ref "U2") (pin "12") (pinfunction "IO11_12") (pintype "bidirectional"))
    )
    (net (code "12") (name "GDR") (class "Default")
      (node (ref "J1") (pin "2") (pinfunction "2_2") (pintype "bidirectional"))
      (node (ref "Q3") (pin "1") (pinfunction "G_1") (pintype "bidirectional"))
      (node (ref "R4") (pin "2") (pinfunction "2_2") (pintype "passive"))
    )
    (net (code "13") (name "GND") (class "Default")
      (node (ref "BOOT_BUTTON") (pin "1") (pinfunction "1_1") (pintype "passive"))
      (node (ref "BOOT_BUTTON") (pin "2") (pinfunction "2_2") (pintype "passive"))
      (node (ref "C1") (pin "2") (pinfunction "2_2") (pintype "passive"))
      (node (ref "C10") (pin "2") (pinfunction "2_2") (pintype "passive"))
      (node (ref "C10_SUPERCAP") (pin "1") (pinfunction "1_1") (pintype "passive"))
      (node (ref "C1_BAT") (pin "1") (pinfunction "1_1") (pintype "passive"))
      (node (ref "C1_BAT1") (pin "2") (pinfunction "2_2") (pintype "passive"))
      (node (ref "C1_BAT2") (pin "2") (pinfunction "2_2") (pintype "passive"))
      (node (ref "C2") (pin "2") (pinfunction "2_2") (pintype "passive"))
      (node (ref "C2_BAT") (pin "1") (pinfunction "1_1") (pintype "passive"))
      (node (ref "C3") (pin "-") (pinfunction "-_-") (pintype "passive"))
      (node (ref "C4_USB") (pin "2") (pinfunction "2_2") (pintype "passive"))
      (node (ref "C5") (pin "2") (pinfunction "2_2") (pintype "passive"))
      (node (ref "C5_USB") (pin "2") (pinfunction "2_2") (pintype "passive"))
      (node (ref "C6") (pin "2") (pinfunction "2_2") (pintype "passive"))
      (node (ref "C7") (pin "2") (pinfunction "2_2") (pintype "passive"))
      (node (ref "C8") (pin "2") (pinfunction "2_2") (pintype "passive"))
      (node (ref "C9") (pin "2") (pinfunction "2_2") (pintype "passive"))
      (node (ref "CHANGE_BUTTON") (pin "1") (pinfunction "1_1") (pintype "passive"))
      (node (ref "CHANGE_BUTTON") (pin "2") (pinfunction "2_2") (pintype "passive"))
      (node (ref "C_DELAY") (pin "2") (pinfunction "2_2") (pintype "passive"))
      (node (ref "D1") (pin "2") (pinfunction "GND_2") (pintype "bidirectional"))
      (node (ref "D10") (pin "1") (pinfunction "1_1") (pintype "passive"))
      (node (ref "D11") (pin "1") (pinfunction "1_1") (pintype "passive"))
      (node (ref "D12") (pin "1") (pinfunction "1_1") (pintype "passive"))
      (node (ref "D3") (pin "1") (pinfunction "K_1") (pintype "bidirectional"))
      (node (ref "D6") (pin "1") (pinfunction "1_1") (pintype "passive"))
      (node (ref "D8") (pin "1") (pinfunction "1_1") (pintype "passive"))
      (node (ref "D9") (pin "1") (pinfunction "1_1") (pintype "passive"))
      (node (ref "EPD_C1") (pin "2") (pinfunction "2_2") (pintype "passive"))
      (node (ref "EPD_C10") (pin "2") (pinfunction "2_2") (pintype "passive"))
      (node (ref "EPD_C11") (pin "2") (pinfunction "2_2") (pintype "passive"))
      (node (ref "EPD_C12") (pin "2") (pinfunction "2_2") (pintype "passive"))
      (node (ref "EPD_C2") (pin "2") (pinfunction "2_2") (pintype "passive"))
      (node (ref "EPD_C5") (pin "2") (pinfunction "2_2") (pintype "passive"))
      (node (ref "EPD_C6") (pin "2") (pinfunction "2_2") (pintype "passive"))
      (node (ref "EPD_C7") (pin "2") (pinfunction "2_2") (pintype "passive"))
      (node (ref "EPD_C8") (pin "2") (pinfunction "2_2") (pintype "passive"))
      (node (ref "EPD_C9") (pin "2") (pinfunction "2_2") (pintype "passive"))
      (node (ref "IC1") (pin "3") (pinfunction "GND_3") (pintype "bidirectional"))
      (node (ref "IC4") (pin "1") (pinfunction "VIN_1") (pintype "bidirectional"))
      (node (ref "IC4") (pin "2") (pinfunction "VSS_2") (pintype "bidirectional"))
      (node (ref "IC4") (pin "3") (pinfunction "CE_3") (pintype "bidirectional"))
      (node (ref "J1") (pin "17") (pinfunction "17_17") (pintype "bidirectional"))
      (node (ref "J1") (pin "8") (pinfunction "8_8") (pintype "bidirectional"))
      (node (ref "J1") (pin "MP1") (pinfunction "MP1_MP1") (pintype "bidirectional"))
      (node (ref "J1") (pin "MP2") (pinfunction "MP2_MP2") (pintype "bidirectional"))
      (node (ref "J2") (pin "A1") (pinfunction "A1_A1") (pintype "bidirectional"))
      (node (ref "J2") (pin "A12") (pinfunction "A12_A12") (pintype "bidirectional"))
      (node (ref "J2") (pin "B1") (pinfunction "B1_B1") (pintype "bidirectional"))
      (node (ref "J2") (pin "B12") (pinfunction "B12_B12") (pintype "bidirectional"))
      (node (ref "J2") (pin "MP1") (pinfunction "MP1_MP1") (pintype "bidirectional"))
      (node (ref "J2") (pin "MP2") (pinfunction "MP2_MP2") (pintype "bidirectional"))
      (node (ref "J2") (pin "MP3") (pinfunction "MP3_MP3") (pintype "bidirectional"))
      (node (ref "J2") (pin "MP4") (pinfunction "MP4_MP4") (pintype "bidirectional"))
      (node (ref "J3") (pin "1") (pinfunction "1_1") (pintype "power_in"))
      (node (ref "J4") (pin "G1") (pinfunction "GND_1_G1") (pintype "bidirectional"))
      (node (ref "J4") (pin "G2") (pinfunction "GND_2_G2") (pintype "bidirectional"))
      (node (ref "J4") (pin "G3") (pinfunction "GND_3_G3") (pintype "bidirectional"))
      (node (ref "J4") (pin "G4") (pinfunction "GND_4_G4") (pintype "bidirectional"))
      (node (ref "J4") (pin "P6") (pinfunction "VSS_P6") (pintype "bidirectional"))
      (node (ref "MCP73831") (pin "2") (pinfunction "VSS_2") (pintype "power_in"))
      (node (ref "R1_PWRUSB") (pin "1") (pinfunction "1_1") (pintype "passive"))
      (node (ref "R2-USB") (pin "2") (pinfunction "2_2") (pintype "passive"))
      (node (ref "R2-USB1") (pin "1") (pinfunction "1_1") (pintype "passive"))
      (node (ref "R2_BAT") (pin "1") (pinfunction "1_1") (pintype "passive"))
      (node (ref "R4") (pin "1") (pinfunction "1_1") (pintype "passive"))
      (node (ref "RESET_BUTTON") (pin "1") (pinfunction "1_1") (pintype "passive"))
      (node (ref "RESET_BUTTON") (pin "2") (pinfunction "2_2") (pintype "passive"))
      (node (ref "SENSOR2") (pin "1") (pinfunction "GND_1") (pintype "power_in"))
      (node (ref "SENSOR2") (pin "5") (pinfunction "SDO_5") (pintype "bidirectional"))
      (node (ref "SENSOR2") (pin "7") (pinfunction "GND_7") (pintype "power_in"))
      (node (ref "SJ1") (pin "1") (pinfunction "1_1") (pintype "passive"))
      (node (ref "TP4") (pin "TP") (pinfunction "TP_TP") (pintype "input"))
      (node (ref "TP5") (pin "TP") (pinfunction "TP_TP") (pintype "input"))
      (node (ref "U1") (pin "4") (pinfunction "GND_4") (pintype "power_in"))
      (node (ref "U1") (pin "9") (pinfunction "EXP_9") (pintype "passive"))
      (node (ref "U2") (pin "1") (pinfunction "GND_1") (pintype "power_in"))
      (node (ref "U2") (pin "28") (pinfunction "GND_28") (pintype "power_in"))
      (node (ref "U2") (pin "29_1") (pinfunction "GND_29_1") (pintype "power_in"))
      (node (ref "U2") (pin "29_2") (pinfunction "GND_29_2") (pintype "power_in"))
      (node (ref "U2") (pin "29_3") (pinfunction "GND_29_3") (pintype "power_in"))
      (node (ref "U2") (pin "29_4") (pinfunction "GND_29_4") (pintype "power_in"))
      (node (ref "U2") (pin "29_5") (pinfunction "GND_29_5") (pintype "power_in"))
      (node (ref "U2") (pin "29_6") (pinfunction "GND_29_6") (pintype "power_in"))
      (node (ref "U2") (pin "29_7") (pinfunction "GND_29_7") (pintype "power_in"))
      (node (ref "U2") (pin "29_8") (pinfunction "GND_29_8") (pintype "power_in"))
      (node (ref "U2") (pin "29_9") (pinfunction "GND_29_9") (pintype "power_in"))
      (node (ref "U3") (pin "13") (pinfunction "GND_13") (pintype "power_in"))
      (node (ref "U4") (pin "1") (pinfunction "CTG_1") (pintype "power_in"))
      (node (ref "U4") (pin "4") (pinfunction "GND_4") (pintype "power_in"))
      (node (ref "U4") (pin "6") (pinfunction "QSTRT_6") (pintype "input"))
      (node (ref "U4") (pin "9") (pinfunction "EP_9") (pintype "power_in"))
    )
    (net (code "14") (name "GPIO8") (class "Default")
      (node (ref "R1") (pin "2") (pinfunction "2_2") (pintype "passive"))
      (node (ref "U2") (pin "10") (pinfunction "IO8_10") (pintype "bidirectional"))
    )
    (net (code "15") (name "I2C_PW") (class "Default")
      (node (ref "C1") (pin "1") (pinfunction "1_1") (pintype "passive"))
      (node (ref "C2") (pin "1") (pinfunction "1_1") (pintype "passive"))
      (node (ref "R1_PINH") (pin "1") (pinfunction "1_1") (pintype "passive"))
      (node (ref "R2-PINH") (pin "1") (pinfunction "1_1") (pintype "passive"))
      (node (ref "SENSOR2") (pin "2") (pinfunction "CSB_2") (pintype "input"))
      (node (ref "SENSOR2") (pin "6") (pinfunction "VDDIO_6") (pintype "power_in"))
      (node (ref "SENSOR2") (pin "8") (pinfunction "VDD_8") (pintype "power_in"))
      (node (ref "U2") (pin "17") (pinfunction "IO19_17") (pintype "bidirectional"))
    )
    (net (code "16") (name "INT_RTC") (class "Default")
      (node (ref "R1_PINH1") (pin "1") (pinfunction "1_1") (pintype "passive"))
      (node (ref "TP15") (pin "TP") (pinfunction "TP_TP") (pintype "input"))
      (node (ref "U2") (pin "8") (pinfunction "IO0_8") (pintype "bidirectional"))
      (node (ref "U3") (pin "3") (pinfunction "SQW/~{INT}_3") (pintype "output"))
    )
    (net (code "17") (name "IO{slash}BOOT") (class "Default")
      (node (ref "BOOT_BUTTON") (pin "3") (pinfunction "3_3") (pintype "passive"))
      (node (ref "BOOT_BUTTON") (pin "4") (pinfunction "4_4") (pintype "passive"))
      (node (ref "C6") (pin "1") (pinfunction "1_1") (pintype "passive"))
      (node (ref "R_BOOT") (pin "2") (pinfunction "2_2") (pintype "passive"))
      (node (ref "U2") (pin "15") (pinfunction "IO9_15") (pintype "bidirectional"))
    )
    (net (code "18") (name "IO{slash}CHANGE") (class "Default")
      (node (ref "C10") (pin "1") (pinfunction "1_1") (pintype "passive"))
      (node (ref "CHANGE_BUTTON") (pin "3") (pinfunction "3_3") (pintype "passive"))
      (node (ref "CHANGE_BUTTON") (pin "4") (pinfunction "4_4") (pintype "passive"))
      (node (ref "R_CHANGE") (pin "2") (pinfunction "2_2") (pintype "passive"))
      (node (ref "U2") (pin "23") (pinfunction "IO15_23") (pintype "bidirectional"))
    )
    (net (code "19") (name "MISO") (class "Default")
      (node (ref "D12") (pin "2") (pinfunction "2_2") (pintype "passive"))
      (node (ref "J4") (pin "P7") (pinfunction "DAT0_P7") (pintype "bidirectional"))
      (node (ref "R8") (pin "1") (pinfunction "1_1") (pintype "passive"))
      (node (ref "TP6") (pin "TP") (pinfunction "TP_TP") (pintype "input"))
      (node (ref "U1") (pin "2") (pinfunction "DO(IO1)_2") (pintype "bidirectional"))
      (node (ref "U2") (pin "27") (pinfunction "IO2_27") (pintype "bidirectional"))
    )
    (net (code "20") (name "MOSI") (class "Default")
      (node (ref "D11") (pin "2") (pinfunction "2_2") (pintype "passive"))
      (node (ref "J1") (pin "14") (pinfunction "14_14") (pintype "bidirectional"))
      (node (ref "J4") (pin "P3") (pinfunction "CMD_P3") (pintype "bidirectional"))
      (node (ref "R7") (pin "1") (pinfunction "1_1") (pintype "passive"))
      (node (ref "TP7") (pin "TP") (pinfunction "TP_TP") (pintype "input"))
      (node (ref "U1") (pin "5") (pinfunction "DI(IO0)_5") (pintype "bidirectional"))
      (node (ref "U2") (pin "7") (pinfunction "IO7_7") (pintype "bidirectional"))
    )
    (net (code "21") (name "Net-(CHG_LED-PadC)") (class "Default")
      (node (ref "CHG_LED") (pin "C") (pinfunction "C_C") (pintype "passive"))
      (node (ref "R1_BAT") (pin "1") (pinfunction "1_1") (pintype "passive"))
    )
    (net (code "22") (name "Net-(D2-CATHODE)") (class "Default")
      (node (ref "C1_BAT1") (pin "1") (pinfunction "1_1") (pintype "passive"))
      (node (ref "D2") (pin "1") (pinfunction "CATHODE_1") (pintype "bidirectional"))
      (node (ref "Q1") (pin "2") (pinfunction "S_2") (pintype "bidirectional"))
    )
    (net (code "23") (name "Net-(D3-A)") (class "Default")
      (node (ref "C4") (pin "1") (pinfunction "1_1") (pintype "passive"))
      (node (ref "D3") (pin "2") (pinfunction "A_2") (pintype "bidirectional"))
      (node (ref "D4") (pin "1") (pinfunction "K_1") (pintype "bidirectional"))
    )
    (net (code "24") (name "Net-(D7-CATHODE)") (class "Default")
      (node (ref "D7") (pin "1") (pinfunction "CATHODE_1") (pintype "bidirectional"))
      (node (ref "R_CAPACITOR") (pin "1") (pinfunction "1_1") (pintype "passive"))
    )
    (net (code "25") (name "Net-(EPD_C1-Pad1)") (class "Default")
      (node (ref "EPD_C1") (pin "1") (pinfunction "1_1") (pintype "passive"))
      (node (ref "J1") (pin "5") (pinfunction "5_5") (pintype "bidirectional"))
    )
    (net (code "26") (name "Net-(EPD_C2-Pad1)") (class "Default")
      (node (ref "EPD_C2") (pin "1") (pinfunction "1_1") (pintype "passive"))
      (node (ref "J1") (pin "4") (pinfunction "4_4") (pintype "bidirectional"))
    )
    (net (code "27") (name "Net-(EPD_C6-Pad1)") (class "Default")
      (node (ref "EPD_C6") (pin "1") (pinfunction "1_1") (pintype "passive"))
      (node (ref "J1") (pin "18") (pinfunction "18_18") (pintype "bidirectional"))
    )
    (net (code "28") (name "Net-(EPD_C7-Pad1)") (class "Default")
      (node (ref "EPD_C7") (pin "1") (pinfunction "1_1") (pintype "passive"))
      (node (ref "J1") (pin "19") (pinfunction "19_19") (pintype "bidirectional"))
    )
    (net (code "29") (name "Net-(EPD_C8-Pad1)") (class "Default")
      (node (ref "EPD_C8") (pin "1") (pinfunction "1_1") (pintype "passive"))
      (node (ref "J1") (pin "20") (pinfunction "20_20") (pintype "bidirectional"))
    )
    (net (code "30") (name "Net-(EPD_C10-Pad1)") (class "Default")
      (node (ref "EPD_C10") (pin "1") (pinfunction "1_1") (pintype "passive"))
      (node (ref "J1") (pin "22") (pinfunction "22_22") (pintype "bidirectional"))
    )
    (net (code "31") (name "Net-(EPD_C12-Pad1)") (class "Default")
      (node (ref "EPD_C12") (pin "1") (pinfunction "1_1") (pintype "passive"))
      (node (ref "J1") (pin "24") (pinfunction "24_24") (pintype "bidirectional"))
    )
    (net (code "32") (name "Net-(IC1-CT)") (class "Default")
      (node (ref "C_DELAY") (pin "1") (pinfunction "1_1") (pintype "passive"))
      (node (ref "IC1") (pin "5") (pinfunction "CT_5") (pintype "bidirectional"))
    )
    (net (code "33") (name "Net-(J2-PadA5)") (class "Default")
      (node (ref "J2") (pin "A5") (pinfunction "A5_A5") (pintype "bidirectional"))
      (node (ref "R2-USB1") (pin "2") (pinfunction "2_2") (pintype "passive"))
    )
    (net (code "34") (name "Net-(J2-PadB5)") (class "Default")
      (node (ref "J2") (pin "B5") (pinfunction "B5_B5") (pintype "bidirectional"))
      (node (ref "R2-USB") (pin "1") (pinfunction "1_1") (pintype "passive"))
    )
    (net (code "35") (name "Net-(MCP73831-PROG)") (class "Default")
      (node (ref "MCP73831") (pin "5") (pinfunction "PROG_5") (pintype "input"))
      (node (ref "R2_BAT") (pin "2") (pinfunction "2_2") (pintype "passive"))
    )
    (net (code "36") (name "Net-(MCP73831-STAT)") (class "Default")
      (node (ref "MCP73831") (pin "1") (pinfunction "STAT_1") (pintype "output"))
      (node (ref "R1_BAT") (pin "2") (pinfunction "2_2") (pintype "passive"))
    )
    (net (code "37") (name "PREVGH") (class "Default")
      (node (ref "D5") (pin "1") (pinfunction "K_1") (pintype "bidirectional"))
      (node (ref "EPD_C9") (pin "1") (pinfunction "1_1") (pintype "passive"))
      (node (ref "J1") (pin "21") (pinfunction "21_21") (pintype "bidirectional"))
    )
    (net (code "38") (name "PREVGL") (class "Default")
      (node (ref "D4") (pin "2") (pinfunction "A_2") (pintype "bidirectional"))
      (node (ref "EPD_C11") (pin "1") (pinfunction "1_1") (pintype "passive"))
      (node (ref "J1") (pin "23") (pinfunction "23_23") (pintype "bidirectional"))
    )
    (net (code "39") (name "RESE") (class "Default")
      (node (ref "J1") (pin "3") (pinfunction "3_3") (pintype "bidirectional"))
      (node (ref "Q3") (pin "2") (pinfunction "S_2") (pintype "bidirectional"))
      (node (ref "R3") (pin "1") (pinfunction "1_1") (pintype "passive"))
    )
    (net (code "40") (name "RESE'") (class "Default")
      (node (ref "R2") (pin "2") (pinfunction "2_2") (pintype "passive"))
      (node (ref "R3") (pin "2") (pinfunction "2_2") (pintype "passive"))
      (node (ref "SJ1") (pin "2") (pinfunction "2_2") (pintype "passive"))
    )
    (net (code "41") (name "RESET") (class "Default")
      (node (ref "C5") (pin "1") (pinfunction "1_1") (pintype "passive"))
      (node (ref "IC1") (pin "1") (pinfunction "VOUT_1") (pintype "bidirectional"))
      (node (ref "RESET_BUTTON") (pin "3") (pinfunction "3_3") (pintype "passive"))
      (node (ref "RESET_BUTTON") (pin "4") (pinfunction "4_4") (pintype "passive"))
      (node (ref "R_RESET") (pin "2") (pinfunction "2_2") (pintype "passive"))
      (node (ref "U2") (pin "3") (pinfunction "EN_3") (pintype "input"))
    )
    (net (code "42") (name "RTC_RST") (class "Default")
      (node (ref "U2") (pin "16") (pinfunction "IO18_16") (pintype "bidirectional"))
      (node (ref "U3") (pin "4") (pinfunction "~{RST}_4") (pintype "input"))
    )
    (net (code "43") (name "RX") (class "Default")
      (node (ref "TP2") (pin "TP") (pinfunction "TP_TP") (pintype "input"))
      (node (ref "U2") (pin "24") (pinfunction "RXD0/GPIO17_24") (pintype "bidirectional"))
    )
    (net (code "44") (name "SCK") (class "Default")
      (node (ref "D10") (pin "2") (pinfunction "2_2") (pintype "passive"))
      (node (ref "J1") (pin "13") (pinfunction "13_13") (pintype "bidirectional"))
      (node (ref "J4") (pin "P5") (pinfunction "CLK_P5") (pintype "bidirectional"))
      (node (ref "R6") (pin "1") (pinfunction "1_1") (pintype "passive"))
      (node (ref "TP8") (pin "TP") (pinfunction "TP_TP") (pintype "input"))
      (node (ref "U1") (pin "6") (pinfunction "CLK_6") (pintype "input"))
      (node (ref "U2") (pin "6") (pinfunction "IO6_6") (pintype "bidirectional"))
    )
    (net (code "45") (name "SCL") (class "Default")
      (node (ref "J3") (pin "4") (pinfunction "4_4") (pintype "passive"))
      (node (ref "SENSOR2") (pin "4") (pinfunction "SCK_4") (pintype "input"))
      (node (ref "U2") (pin "20") (pinfunction "IO22_20") (pintype "bidirectional"))
      (node (ref "U3") (pin "16") (pinfunction "SCL_16") (pintype "input"))
      (node (ref "U4") (pin "7") (pinfunction "SCL_7") (pintype "input"))
    )
    (net (code "46") (name "SDA") (class "Default")
      (node (ref "J3") (pin "3") (pinfunction "3_3") (pintype "passive"))
      (node (ref "SENSOR2") (pin "3") (pinfunction "SDI_3") (pintype "bidirectional"))
      (node (ref "U2") (pin "19") (pinfunction "IO21_19") (pintype "bidirectional"))
      (node (ref "U3") (pin "15") (pinfunction "SDA_15") (pintype "bidirectional"))
      (node (ref "U4") (pin "8") (pinfunction "SDA_8") (pintype "bidirectional"))
    )
    (net (code "47") (name "SRC") (class "Default")
      (node (ref "C4") (pin "2") (pinfunction "2_2") (pintype "passive"))
      (node (ref "D5") (pin "2") (pinfunction "A_2") (pintype "bidirectional"))
      (node (ref "L1") (pin "1") (pinfunction "1_1") (pintype "passive"))
      (node (ref "Q3") (pin "3") (pinfunction "D_3") (pintype "bidirectional"))
    )
    (net (code "48") (name "SS_SD") (class "Default")
      (node (ref "D8") (pin "2") (pinfunction "2_2") (pintype "passive"))
      (node (ref "J4") (pin "P2") (pinfunction "CD/DAT3_P2") (pintype "bidirectional"))
      (node (ref "R10") (pin "1") (pinfunction "1_1") (pintype "passive"))
      (node (ref "U2") (pin "4") (pinfunction "IO4_4") (pintype "bidirectional"))
    )
    (net (code "49") (name "TX") (class "Default")
      (node (ref "TP1") (pin "TP") (pinfunction "TP_TP") (pintype "input"))
      (node (ref "U2") (pin "25") (pinfunction "TXD0/GPIO16_25") (pintype "bidirectional"))
    )
    (net (code "50") (name "USB_D") (class "Default")
      (node (ref "D1") (pin "3") (pinfunction "I/O2_1_3") (pintype "bidirectional"))
    )
    (net (code "51") (name "USB_D+") (class "Default")
      (node (ref "D1") (pin "1") (pinfunction "I/O1_1_1") (pintype "bidirectional"))
      (node (ref "U2") (pin "14") (pinfunction "IO13_14") (pintype "bidirectional"))
    )
    (net (code "52") (name "USB_D-") (class "Default")
      (node (ref "U2") (pin "13") (pinfunction "IO12_13") (pintype "bidirectional"))
    )
    (net (code "53") (name "VBAT") (class "Default")
      (node (ref "C2_BAT") (pin "2") (pinfunction "2_2") (pintype "passive"))
      (node (ref "MCP73831") (pin "3") (pinfunction "VBAT_3") (pintype "power_in"))
      (node (ref "Q1") (pin "3") (pinfunction "D_3") (pintype "bidirectional"))
      (node (ref "TP3") (pin "TP") (pinfunction "TP_TP") (pintype "input"))
      (node (ref "U4") (pin "2") (pinfunction "CELL_2") (pintype "power_in"))
      (node (ref "U4") (pin "3") (pinfunction "VDD_3") (pintype "power_in"))
    )
    (net (code "54") (name "VBUS") (class "Default")
      (node (ref "C1_BAT") (pin "2") (pinfunction "2_2") (pintype "passive"))
      (node (ref "C4_USB") (pin "1") (pinfunction "1_1") (pintype "passive"))
      (node (ref "C5_USB") (pin "1") (pinfunction "1_1") (pintype "passive"))
      (node (ref "CHG_LED") (pin "A") (pinfunction "A_A") (pintype "passive"))
      (node (ref "D1") (pin "5") (pinfunction "VBUS_5") (pintype "bidirectional"))
      (node (ref "D2") (pin "2") (pinfunction "ANODE_2") (pintype "bidirectional"))
      (node (ref "J2") (pin "B9") (pinfunction "B9_B9") (pintype "bidirectional"))
      (node (ref "MCP73831") (pin "4") (pinfunction "VIN_4") (pintype "power_in"))
      (node (ref "PFMF.050.1") (pin "2") (pinfunction "2_2") (pintype "passive"))
      (node (ref "Q1") (pin "1") (pinfunction "G_1") (pintype "bidirectional"))
      (node (ref "R1_PWRUSB") (pin "2") (pinfunction "2_2") (pintype "passive"))
      (node (ref "TP14") (pin "TP") (pinfunction "TP_TP") (pintype "input"))
    )
    (net (code "55") (name "VRTC") (class "Default")
      (node (ref "C10_SUPERCAP") (pin "2") (pinfunction "2_2") (pintype "passive"))
      (node (ref "C8") (pin "1") (pinfunction "1_1") (pintype "passive"))
      (node (ref "R_CAPACITOR") (pin "2") (pinfunction "2_2") (pintype "passive"))
      (node (ref "U3") (pin "14") (pinfunction "VBAT_14") (pintype "power_in"))
    )
    (net (code "56") (name "VUSB") (class "Default")
      (node (ref "J2") (pin "A4") (pinfunction "A4_A4") (pintype "bidirectional"))
      (node (ref "J2") (pin "A9") (pinfunction "A9_A9") (pintype "bidirectional"))
      (node (ref "J2") (pin "B4") (pinfunction "B4_B4") (pintype "bidirectional"))
      (node (ref "PFMF.050.1") (pin "1") (pinfunction "1_1") (pintype "passive"))
    )
    (net (code "57") (name "unconnected-(IC1-NC-Pad4)") (class "Default")
      (node (ref "IC1") (pin "4") (pinfunction "NC_4") (pintype "no_connect"))
    )
    (net (code "58") (name "unconnected-(IC4-NC-Pad4)") (class "Default")
      (node (ref "IC4") (pin "4") (pinfunction "NC_4") (pintype "no_connect"))
    )
    (net (code "59") (name "unconnected-(J1-Pad1)") (class "Default")
      (node (ref "J1") (pin "1") (pinfunction "1_1") (pintype "bidirectional"))
    )
    (net (code "60") (name "unconnected-(J1-Pad6)") (class "Default")
      (node (ref "J1") (pin "6") (pinfunction "6_6") (pintype "bidirectional"))
    )
    (net (code "61") (name "unconnected-(J1-Pad7)") (class "Default")
      (node (ref "J1") (pin "7") (pinfunction "7_7") (pintype "bidirectional"))
    )
    (net (code "62") (name "unconnected-(J2-PadA8)") (class "Default")
      (node (ref "J2") (pin "A8") (pinfunction "A8_A8") (pintype "bidirectional"))
    )
    (net (code "63") (name "unconnected-(J2-PadB8)") (class "Default")
      (node (ref "J2") (pin "B8") (pinfunction "B8_B8") (pintype "bidirectional"))
    )
    (net (code "64") (name "unconnected-(J4-DAT1-PadP8)") (class "Default")
      (node (ref "J4") (pin "P8") (pinfunction "DAT1_P8") (pintype "bidirectional"))
    )
    (net (code "65") (name "unconnected-(J4-DAT2-PadP1)") (class "Default")
      (node (ref "J4") (pin "P1") (pinfunction "DAT2_P1") (pintype "bidirectional"))
    )
    (net (code "66") (name "unconnected-(J4-DETECTION_1-PadS1)") (class "Default")
      (node (ref "J4") (pin "S1") (pinfunction "DETECTION_1_S1") (pintype "bidirectional"))
    )
    (net (code "67") (name "unconnected-(J4-DETECTION_2-PadS2)") (class "Default")
      (node (ref "J4") (pin "S2") (pinfunction "DETECTION_2_S2") (pintype "bidirectional"))
    )
    (net (code "68") (name "unconnected-(R1_PINH-Pad2)") (class "Default")
      (node (ref "R1_PINH") (pin "2") (pinfunction "2_2") (pintype "passive"))
    )
    (net (code "69") (name "unconnected-(R2-PINH-Pad2)") (class "Default")
      (node (ref "R2-PINH") (pin "2") (pinfunction "2_2") (pintype "passive"))
    )
    (net (code "70") (name "unconnected-(R2-Pad1)") (class "Default")
      (node (ref "R2") (pin "1") (pinfunction "1_1") (pintype "passive"))
    )
    (net (code "71") (name "unconnected-(U2-NC-Pad22)") (class "Default")
      (node (ref "U2") (pin "22") (pinfunction "NC_22") (pintype "no_connect"))
    )
    (net (code "72") (name "unconnected-(U4-~{ALERT}-Pad5)") (class "Default")
      (node (ref "U4") (pin "5") (pinfunction "~{ALERT}_5") (pintype "output"))
    )
  )
)
